# UI.net
KiCad netlist of a schematic drawn in Altium Designer
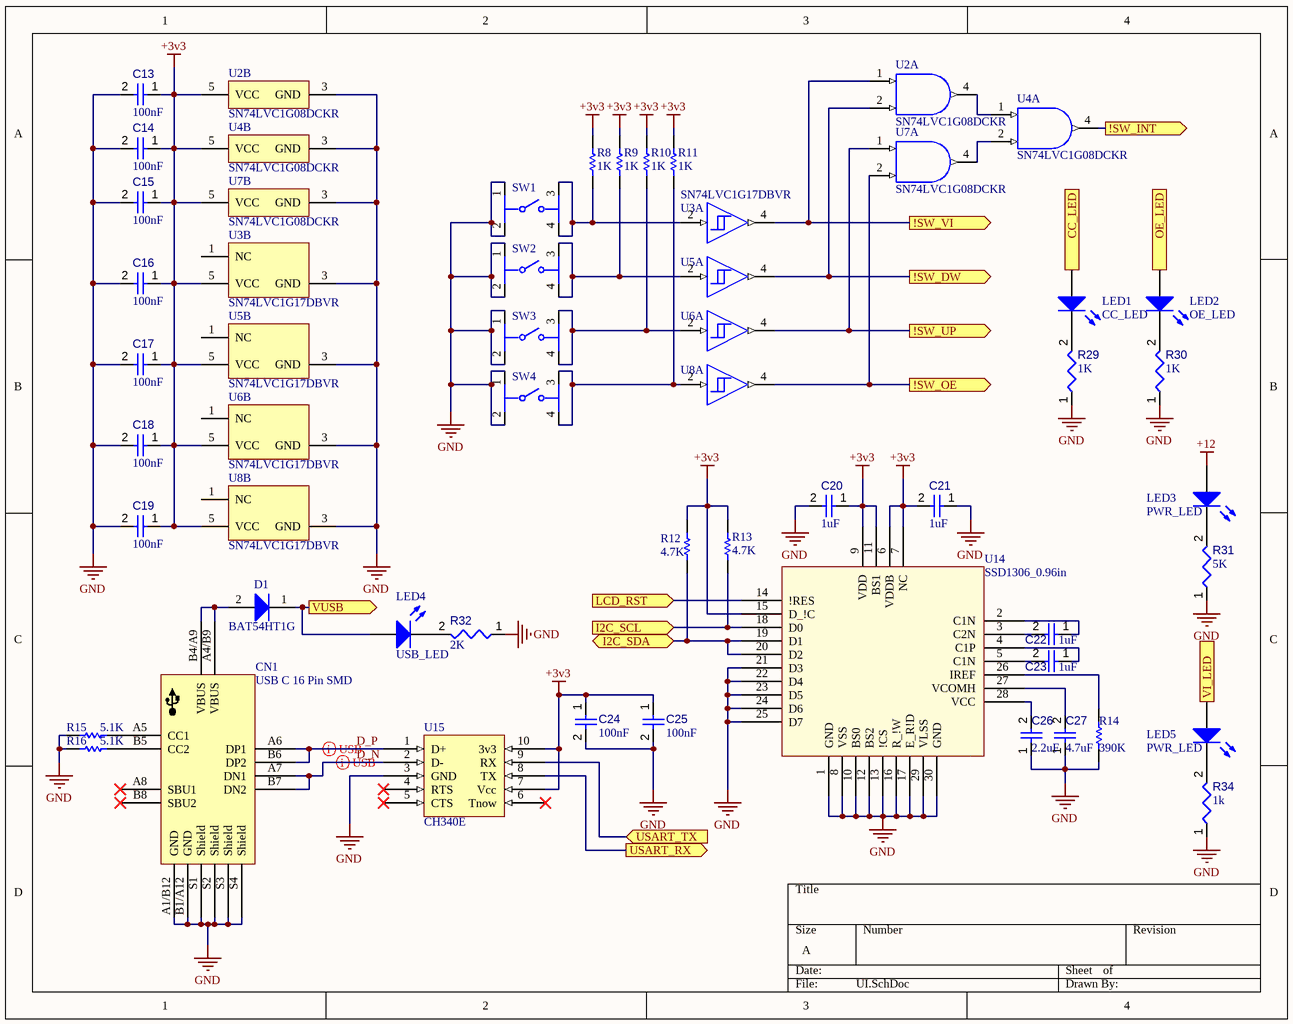
[diagram p0: UI.SchDoc]

(export (version "E")
  (design (tool "Eeschema 10.0.6"))
  (components
    (comp (ref "C13")
      (value "100nF")
      (footprint "CAPC2013X95X50ML10T25")
      (description "Chip Capacitor, 100 nF, +/- 10%, 50 V, 0805 (2012 Metric)")
      (fields (field (name "TOLERANCE") "10%") (field (name "Comment") "Capacitor 100 nF +/-10% 50 V 0805"))
      (libsource (lib "Aditya Sehgal") (part "CAP-NP-2"))
    )
    (comp (ref "C14")
      (value "100nF")
      (footprint "CAPC2013X95X50ML10T25")
      (description "Chip Capacitor, 100 nF, +/- 10%, 50 V, 0805 (2012 Metric)")
      (fields (field (name "TOLERANCE") "10%") (field (name "Comment") "Capacitor 100 nF +/-10% 50 V 0805"))
      (libsource (lib "Aditya Sehgal") (part "CAP-NP-2"))
    )
    (comp (ref "C15")
      (value "100nF")
      (footprint "CAPC2013X95X50ML10T25")
      (description "Chip Capacitor, 100 nF, +/- 10%, 50 V, 0805 (2012 Metric)")
      (fields (field (name "TOLERANCE") "10%") (field (name "Comment") "Capacitor 100 nF +/-10% 50 V 0805"))
      (libsource (lib "Aditya Sehgal") (part "CAP-NP-2"))
    )
    (comp (ref "C16")
      (value "100nF")
      (footprint "CAPC2013X95X50ML10T25")
      (description "Chip Capacitor, 100 nF, +/- 10%, 50 V, 0805 (2012 Metric)")
      (fields (field (name "TOLERANCE") "10%") (field (name "Comment") "Capacitor 100 nF +/-10% 50 V 0805"))
      (libsource (lib "Aditya Sehgal") (part "CAP-NP-2"))
    )
    (comp (ref "C17")
      (value "100nF")
      (footprint "CAPC2013X95X50ML10T25")
      (description "Chip Capacitor, 100 nF, +/- 10%, 50 V, 0805 (2012 Metric)")
      (fields (field (name "TOLERANCE") "10%") (field (name "Comment") "Capacitor 100 nF +/-10% 50 V 0805"))
      (libsource (lib "Aditya Sehgal") (part "CAP-NP-2"))
    )
    (comp (ref "C18")
      (value "100nF")
      (footprint "CAPC2013X95X50ML10T25")
      (description "Chip Capacitor, 100 nF, +/- 10%, 50 V, 0805 (2012 Metric)")
      (fields (field (name "TOLERANCE") "10%") (field (name "Comment") "Capacitor 100 nF +/-10% 50 V 0805"))
      (libsource (lib "Aditya Sehgal") (part "CAP-NP-2"))
    )
    (comp (ref "C19")
      (value "100nF")
      (footprint "CAPC2013X95X50ML10T25")
      (description "Chip Capacitor, 100 nF, +/- 10%, 50 V, 0805 (2012 Metric)")
      (fields (field (name "TOLERANCE") "10%") (field (name "Comment") "Capacitor 100 nF +/-10% 50 V 0805"))
      (libsource (lib "Aditya Sehgal") (part "CAP-NP-2"))
    )
    (comp (ref "C20")
      (value "1uF")
      (footprint "CAPC2013X95X50ML10T25")
      (description "Chip Capacitor, 100 nF, +/- 10%, 50 V, 0805 (2012 Metric)")
      (fields (field (name "TOLERANCE") "10%") (field (name "Comment") "Capacitor 100 nF +/-10% 50 V 0805"))
      (libsource (lib "Aditya Sehgal") (part "CAP-NP-2"))
    )
    (comp (ref "C21")
      (value "1uF")
      (footprint "CAPC2013X95X50ML10T25")
      (description "Chip Capacitor, 100 nF, +/- 10%, 50 V, 0805 (2012 Metric)")
      (fields (field (name "TOLERANCE") "10%") (field (name "Comment") "Capacitor 100 nF +/-10% 50 V 0805"))
      (libsource (lib "Aditya Sehgal") (part "CAP-NP-2"))
    )
    (comp (ref "C22")
      (value "1uF")
      (footprint "CAPC2013X95X50ML10T25")
      (description "Chip Capacitor, 100 nF, +/- 10%, 50 V, 0805 (2012 Metric)")
      (fields (field (name "TOLERANCE") "10%") (field (name "Comment") "Capacitor 100 nF +/-10% 50 V 0805"))
      (libsource (lib "Aditya Sehgal") (part "CAP-NP-2"))
    )
    (comp (ref "C23")
      (value "1uF")
      (footprint "CAPC2013X95X50ML10T25")
      (description "Chip Capacitor, 100 nF, +/- 10%, 50 V, 0805 (2012 Metric)")
      (fields (field (name "TOLERANCE") "10%") (field (name "Comment") "Capacitor 100 nF +/-10% 50 V 0805"))
      (libsource (lib "Aditya Sehgal") (part "CAP-NP-2"))
    )
    (comp (ref "C24")
      (value "100nF")
      (footprint "CAPC2013X95X50ML10T25")
      (description "Chip Capacitor, 100 nF, +/- 10%, 50 V, 0805 (2012 Metric)")
      (fields (field (name "TOLERANCE") "10%") (field (name "Comment") "Capacitor 100 nF +/-10% 50 V 0805"))
      (libsource (lib "Aditya Sehgal") (part "CAP-NP-2"))
    )
    (comp (ref "C25")
      (value "100nF")
      (footprint "CAPC2013X95X50ML10T25")
      (description "Chip Capacitor, 100 nF, +/- 10%, 50 V, 0805 (2012 Metric)")
      (fields (field (name "TOLERANCE") "10%") (field (name "Comment") "Capacitor 100 nF +/-10% 50 V 0805"))
      (libsource (lib "Aditya Sehgal") (part "CAP-NP-2"))
    )
    (comp (ref "C26")
      (value "2.2uF")
      (footprint "CAPC2013X95X50ML10T25")
      (description "Chip Capacitor, 100 nF, +/- 10%, 50 V, 0805 (2012 Metric)")
      (fields (field (name "TOLERANCE") "10%") (field (name "Comment") "Capacitor 100 nF +/-10% 50 V 0805"))
      (libsource (lib "Aditya Sehgal") (part "CAP-NP-2"))
    )
    (comp (ref "C27")
      (value "4.7uF")
      (footprint "CAPC2013X95X50ML10T25")
      (description "Chip Capacitor, 100 nF, +/- 10%, 50 V, 0805 (2012 Metric)")
      (fields (field (name "TOLERANCE") "10%") (field (name "Comment") "Capacitor 100 nF +/-10% 50 V 0805"))
      (libsource (lib "Aditya Sehgal") (part "CAP-NP-2"))
    )
    (comp (ref "CN1")
      (value "USB C 16 Pin SMD")
      (footprint "USB C 16 Pin SMD-Footprint-1")
      (description "C167321 Jing Extension")
      (libsource (lib "Aditya Sehgal") (part "USB C 16 Pin SMD"))
    )
    (comp (ref "D1")
      (value "BAT54HT1G")
      (footprint "ONSC-SOD-323-2-477-02_V")
      (description "Schottky Barrier Diode, 2-Pin SOD-323, Pb-Free, Tape and Reel")
      (fields (field (name "MANUFACTURER") "On Semiconductor"))
      (libsource (lib "Altium Content Vault") (part "ONSC-D-K1A2-2"))
    )
    (comp (ref "LED1")
      (value "CC_LED")
      (footprint "0805_A")
      (description "SMD mono-color Chip LED, WL-SMCW, Super Red")
      (fields (field (name "MANUFACTURER") "Wuerth Elektronik") (field (name "PARTNUMBER") "150080SS75000"))
      (libsource (lib "Altium Content Vault") (part "WE-LED_K1A2-2"))
    )
    (comp (ref "LED2")
      (value "OE_LED")
      (footprint "0805_A")
      (description "SMD mono-color Chip LED, WL-SMCW, Super Red")
      (fields (field (name "MANUFACTURER") "Wuerth Elektronik") (field (name "PARTNUMBER") "150080SS75000"))
      (libsource (lib "Altium Content Vault") (part "WE-LED_K1A2-2"))
    )
    (comp (ref "LED3")
      (value "PWR_LED")
      (footprint "0805_A")
      (description "SMD mono-color Chip LED, WL-SMCW, Super Red")
      (fields (field (name "MANUFACTURER") "Wuerth Elektronik") (field (name "PARTNUMBER") "150080SS75000"))
      (libsource (lib "Altium Content Vault") (part "WE-LED_K1A2-2"))
    )
    (comp (ref "LED4")
      (value "USB_LED")
      (footprint "0805_A")
      (description "SMD mono-color Chip LED, WL-SMCW, Super Red")
      (fields (field (name "MANUFACTURER") "Wuerth Elektronik") (field (name "PARTNUMBER") "150080SS75000"))
      (libsource (lib "Altium Content Vault") (part "WE-LED_K1A2-2"))
    )
    (comp (ref "LED5")
      (value "PWR_LED")
      (footprint "0805_A")
      (description "SMD mono-color Chip LED, WL-SMCW, Super Red")
      (fields (field (name "MANUFACTURER") "Wuerth Elektronik") (field (name "PARTNUMBER") "150080SS75000"))
      (libsource (lib "Altium Content Vault") (part "WE-LED_K1A2-2"))
    )
    (comp (ref "R8")
      (value "1K")
      (footprint "RESC2013X50X35ML15T15")
      (description "Chip Resistor, 0 Ohm, +/- 1%, 125 mW, -55 to 155 degC, 0805 (2012 Metric)")
      (fields (field (name "TOLERANCE") "1%") (field (name "POWER") "125mW"))
      (libsource (lib "Aditya Sehgal") (part "RES-2"))
    )
    (comp (ref "R9")
      (value "1K")
      (footprint "RESC2013X50X35ML15T15")
      (description "Chip Resistor, 0 Ohm, +/- 1%, 125 mW, -55 to 155 degC, 0805 (2012 Metric)")
      (fields (field (name "TOLERANCE") "1%") (field (name "POWER") "125mW"))
      (libsource (lib "Aditya Sehgal") (part "RES-2"))
    )
    (comp (ref "R10")
      (value "1K")
      (footprint "RESC2013X50X35ML15T15")
      (description "Chip Resistor, 0 Ohm, +/- 1%, 125 mW, -55 to 155 degC, 0805 (2012 Metric)")
      (fields (field (name "TOLERANCE") "1%") (field (name "POWER") "125mW"))
      (libsource (lib "Aditya Sehgal") (part "RES-2"))
    )
    (comp (ref "R11")
      (value "1K")
      (footprint "RESC2013X50X35ML15T15")
      (description "Chip Resistor, 0 Ohm, +/- 1%, 125 mW, -55 to 155 degC, 0805 (2012 Metric)")
      (fields (field (name "TOLERANCE") "1%") (field (name "POWER") "125mW"))
      (libsource (lib "Aditya Sehgal") (part "RES-2"))
    )
    (comp (ref "R12")
      (value "4.7K")
      (footprint "RESC2013X50X35ML15T15")
      (description "Chip Resistor, 0 Ohm, +/- 1%, 125 mW, -55 to 155 degC, 0805 (2012 Metric)")
      (fields (field (name "TOLERANCE") "1%") (field (name "POWER") "125mW"))
      (libsource (lib "Aditya Sehgal") (part "RES-2"))
    )
    (comp (ref "R13")
      (value "4.7K")
      (footprint "RESC2013X50X35ML15T15")
      (description "Chip Resistor, 0 Ohm, +/- 1%, 125 mW, -55 to 155 degC, 0805 (2012 Metric)")
      (fields (field (name "TOLERANCE") "1%") (field (name "POWER") "125mW"))
      (libsource (lib "Aditya Sehgal") (part "RES-2"))
    )
    (comp (ref "R14")
      (value "390K")
      (footprint "RESC2013X50X35ML15T15")
      (description "Chip Resistor, 0 Ohm, +/- 1%, 125 mW, -55 to 155 degC, 0805 (2012 Metric)")
      (fields (field (name "TOLERANCE") "1%") (field (name "POWER") "125mW"))
      (libsource (lib "Aditya Sehgal") (part "RES-2"))
    )
    (comp (ref "R15")
      (value "5.1K")
      (footprint "RESC2013X50X35ML15T15")
      (description "Chip Resistor, 0 Ohm, +/- 1%, 125 mW, -55 to 155 degC, 0805 (2012 Metric)")
      (fields (field (name "TOLERANCE") "1%") (field (name "POWER") "125mW"))
      (libsource (lib "Aditya Sehgal") (part "RES-2"))
    )
    (comp (ref "R16")
      (value "5.1K")
      (footprint "RESC2013X50X35ML15T15")
      (description "Chip Resistor, 0 Ohm, +/- 1%, 125 mW, -55 to 155 degC, 0805 (2012 Metric)")
      (fields (field (name "TOLERANCE") "1%") (field (name "POWER") "125mW"))
      (libsource (lib "Aditya Sehgal") (part "RES-2"))
    )
    (comp (ref "R29")
      (value "1K")
      (footprint "RESC0805(2012)_L")
      (description "Chip Resistor, 470 Ohms, +/-5%, 125 mW, -55 to 155 degC, 0805")
      (fields (field (name "POWER") "125mW") (field (name "TOLERANCE") "5%"))
      (libsource (lib "University of California Santa Cruz") (part "RES-2"))
    )
    (comp (ref "R30")
      (value "1K")
      (footprint "RESC0805(2012)_L")
      (description "Chip Resistor, 470 Ohms, +/-5%, 125 mW, -55 to 155 degC, 0805")
      (fields (field (name "POWER") "125mW") (field (name "TOLERANCE") "5%"))
      (libsource (lib "University of California Santa Cruz") (part "RES-2"))
    )
    (comp (ref "R31")
      (value "5K")
      (footprint "RESC0805(2012)_L")
      (description "Chip Resistor, 470 Ohms, +/-5%, 125 mW, -55 to 155 degC, 0805")
      (fields (field (name "POWER") "125mW") (field (name "TOLERANCE") "5%"))
      (libsource (lib "University of California Santa Cruz") (part "RES-2"))
    )
    (comp (ref "R32")
      (value "2K")
      (footprint "RESC0805(2012)_L")
      (description "Chip Resistor, 470 Ohms, +/-5%, 125 mW, -55 to 155 degC, 0805")
      (fields (field (name "POWER") "125mW") (field (name "TOLERANCE") "5%"))
      (libsource (lib "University of California Santa Cruz") (part "RES-2"))
    )
    (comp (ref "R34")
      (value "1k")
      (footprint "RESC0805(2012)_L")
      (description "Chip Resistor, 470 Ohms, +/-5%, 125 mW, -55 to 155 degC, 0805")
      (fields (field (name "POWER") "125mW") (field (name "TOLERANCE") "5%"))
      (libsource (lib "University of California Santa Cruz") (part "RES-2"))
    )
    (comp (ref "SW1")
      (value "PTS526SK15SMTR2LFS")
      (footprint "FP-PTS526SK15SMTR2LFS-MFG")
      (description "Tactile Switch SPST-NO Top Actuated Surface Mount")
      (fields (field (name "MANUFACTURER") "C&K"))
      (libsource (lib "Altium Content Vault") (part "b8895f3f4cefb76e1819d2863dba89b"))
    )
    (comp (ref "SW2")
      (value "PTS526SK15SMTR2LFS")
      (footprint "FP-PTS526SK15SMTR2LFS-MFG")
      (description "Tactile Switch SPST-NO Top Actuated Surface Mount")
      (fields (field (name "MANUFACTURER") "C&K"))
      (libsource (lib "Altium Content Vault") (part "b8895f3f4cefb76e1819d2863dba89b"))
    )
    (comp (ref "SW3")
      (value "PTS526SK15SMTR2LFS")
      (footprint "FP-PTS526SK15SMTR2LFS-MFG")
      (description "Tactile Switch SPST-NO Top Actuated Surface Mount")
      (fields (field (name "MANUFACTURER") "C&K"))
      (libsource (lib "Altium Content Vault") (part "b8895f3f4cefb76e1819d2863dba89b"))
    )
    (comp (ref "SW4")
      (value "PTS526SK15SMTR2LFS")
      (footprint "FP-PTS526SK15SMTR2LFS-MFG")
      (description "Tactile Switch SPST-NO Top Actuated Surface Mount")
      (fields (field (name "MANUFACTURER") "C&K"))
      (libsource (lib "Altium Content Vault") (part "b8895f3f4cefb76e1819d2863dba89b"))
    )
    (comp (ref "U2")
      (value "SN74LVC1G08DCKR")
      (footprint "DCK0005A_M")
      (description "Single 2-Input Positive-AND Gate, DCK0005A, LARGE T&R")
      (fields
        (field (name "GENERIC PART NUMBER") "SN74LVC1G08")
        (field (name "MANUFACTURER") "Texas Instruments")
      )
      (libsource (lib "Altium Content Vault") (part "TI-SN74XXX1X08-5"))
    )
    (comp (ref "U3")
      (value "SN74LVC1G17DBVR")
      (footprint "DBV0005A_L")
      (description "Single Schmitt-Trigger Buffer, DBV0005A, LARGE T&R")
      (fields
        (field (name "MANUFACTURER") "Texas Instruments")
        (field (name "GENERIC PART NUMBER") "SN74LVC1G17")
      )
      (libsource (lib "Altium Content Vault") (part "TI-SN74XXX1XXX-XX-5-SCHMITT"))
    )
    (comp (ref "U4")
      (value "SN74LVC1G08DCKR")
      (footprint "DCK0005A_M")
      (description "Single 2-Input Positive-AND Gate, DCK0005A, LARGE T&R")
      (fields
        (field (name "GENERIC PART NUMBER") "SN74LVC1G08")
        (field (name "MANUFACTURER") "Texas Instruments")
      )
      (libsource (lib "Altium Content Vault") (part "TI-SN74XXX1X08-5"))
    )
    (comp (ref "U5")
      (value "SN74LVC1G17DBVR")
      (footprint "DBV0005A_L")
      (description "Single Schmitt-Trigger Buffer, DBV0005A, LARGE T&R")
      (fields
        (field (name "MANUFACTURER") "Texas Instruments")
        (field (name "GENERIC PART NUMBER") "SN74LVC1G17")
      )
      (libsource (lib "Altium Content Vault") (part "TI-SN74XXX1XXX-XX-5-SCHMITT"))
    )
    (comp (ref "U6")
      (value "SN74LVC1G17DBVR")
      (footprint "DBV0005A_L")
      (description "Single Schmitt-Trigger Buffer, DBV0005A, LARGE T&R")
      (fields
        (field (name "MANUFACTURER") "Texas Instruments")
        (field (name "GENERIC PART NUMBER") "SN74LVC1G17")
      )
      (libsource (lib "Altium Content Vault") (part "TI-SN74XXX1XXX-XX-5-SCHMITT"))
    )
    (comp (ref "U7")
      (value "SN74LVC1G08DCKR")
      (footprint "DCK0005A_M")
      (description "Single 2-Input Positive-AND Gate, DCK0005A, LARGE T&R")
      (fields
        (field (name "GENERIC PART NUMBER") "SN74LVC1G08")
        (field (name "MANUFACTURER") "Texas Instruments")
      )
      (libsource (lib "Altium Content Vault") (part "TI-SN74XXX1X08-5"))
    )
    (comp (ref "U8")
      (value "SN74LVC1G17DBVR")
      (footprint "DBV0005A_L")
      (description "Single Schmitt-Trigger Buffer, DBV0005A, LARGE T&R")
      (fields
        (field (name "MANUFACTURER") "Texas Instruments")
        (field (name "GENERIC PART NUMBER") "SN74LVC1G17")
      )
      (libsource (lib "Altium Content Vault") (part "TI-SN74XXX1XXX-XX-5-SCHMITT"))
    )
    (comp (ref "U14")
      (value "SSD1306_0.96in")
      (footprint "SSD1306_0.96in-Footprint-1")
      (description "C91755")
      (libsource (lib "Aditya Sehgal") (part "SSD1306_0.96in"))
    )
    (comp (ref "U15")
      (value "CH340E")
      (footprint "TSSOP50P490X110-10N")
      (description "USB to UART Converter")
      (libsource (lib "Aditya Sehgal") (part "CH340E"))
    )
  )
  (nets
    (net (code "1") (name "+3v3") (class "Default")
      (node (ref "C13") (pin "1") (pinfunction "1_1") (pintype "passive"))
      (node (ref "C14") (pin "1") (pinfunction "1_1") (pintype "passive"))
      (node (ref "C15") (pin "1") (pinfunction "1_1") (pintype "passive"))
      (node (ref "C16") (pin "1") (pinfunction "1_1") (pintype "passive"))
      (node (ref "C17") (pin "1") (pinfunction "1_1") (pintype "passive"))
      (node (ref "C18") (pin "1") (pinfunction "1_1") (pintype "passive"))
      (node (ref "C19") (pin "1") (pinfunction "1_1") (pintype "passive"))
      (node (ref "C20") (pin "1") (pinfunction "1_1") (pintype "passive"))
      (node (ref "C21") (pin "2") (pinfunction "2_2") (pintype "passive"))
      (node (ref "C24") (pin "1") (pinfunction "1_1") (pintype "passive"))
      (node (ref "C25") (pin "1") (pinfunction "1_1") (pintype "passive"))
      (node (ref "R10") (pin "2") (pinfunction "2_2") (pintype "passive"))
      (node (ref "R11") (pin "2") (pinfunction "2_2") (pintype "passive"))
      (node (ref "R12") (pin "2") (pinfunction "2_2") (pintype "passive"))
      (node (ref "R13") (pin "2") (pinfunction "2_2") (pintype "passive"))
      (node (ref "R8") (pin "2") (pinfunction "2_2") (pintype "passive"))
      (node (ref "R9") (pin "2") (pinfunction "2_2") (pintype "passive"))
      (node (ref "U14") (pin "11") (pinfunction "BS1_11") (pintype "passive"))
      (node (ref "U14") (pin "15") (pinfunction "D_!C_15") (pintype "passive"))
      (node (ref "U14") (pin "6") (pinfunction "VDDB_6") (pintype "passive"))
      (node (ref "U14") (pin "7") (pinfunction "NC_7") (pintype "passive"))
      (node (ref "U14") (pin "9") (pinfunction "VDD_9") (pintype "passive"))
      (node (ref "U15") (pin "10") (pinfunction "3v3_10") (pintype "input"))
      (node (ref "U15") (pin "7") (pinfunction "Vcc_7") (pintype "input"))
      (node (ref "U2") (pin "5") (pinfunction "VCC_5") (pintype "power_in"))
      (node (ref "U3") (pin "5") (pinfunction "VCC_5") (pintype "power_in"))
      (node (ref "U4") (pin "5") (pinfunction "VCC_5") (pintype "power_in"))
      (node (ref "U5") (pin "5") (pinfunction "VCC_5") (pintype "power_in"))
      (node (ref "U6") (pin "5") (pinfunction "VCC_5") (pintype "power_in"))
      (node (ref "U7") (pin "5") (pinfunction "VCC_5") (pintype "power_in"))
      (node (ref "U8") (pin "5") (pinfunction "VCC_5") (pintype "power_in"))
    )
    (net (code "2") (name "+12") (class "Default")
      (node (ref "LED3") (pin "2") (pinfunction "A_2") (pintype "passive"))
    )
    (net (code "3") (name "/!SW_DW") (class "Default")
      (node (ref "U2") (pin "2") (pinfunction "B_2") (pintype "input"))
      (node (ref "U5") (pin "4") (pinfunction "Y_4") (pintype "output"))
    )
    (net (code "4") (name "/!SW_INT") (class "Default")
      (node (ref "U4") (pin "4") (pinfunction "Y_4") (pintype "output"))
    )
    (net (code "5") (name "/!SW_OE") (class "Default")
      (node (ref "U7") (pin "2") (pinfunction "B_2") (pintype "input"))
      (node (ref "U8") (pin "4") (pinfunction "Y_4") (pintype "output"))
    )
    (net (code "6") (name "/!SW_UP") (class "Default")
      (node (ref "U6") (pin "4") (pinfunction "Y_4") (pintype "output"))
      (node (ref "U7") (pin "1") (pinfunction "A_1") (pintype "input"))
    )
    (net (code "7") (name "/!SW_VI") (class "Default")
      (node (ref "U2") (pin "1") (pinfunction "A_1") (pintype "input"))
      (node (ref "U3") (pin "4") (pinfunction "Y_4") (pintype "output"))
    )
    (net (code "8") (name "/CC_LED") (class "Default")
      (node (ref "LED1") (pin "2") (pinfunction "A_2") (pintype "passive"))
    )
    (net (code "9") (name "/D_N") (class "Default")
      (node (ref "CN1") (pin "A7") (pinfunction "DN1_A7") (pintype "passive"))
      (node (ref "CN1") (pin "B7") (pinfunction "DN2_B7") (pintype "passive"))
      (node (ref "U15") (pin "2") (pinfunction "D-_2") (pintype "input"))
    )
    (net (code "10") (name "/D_P") (class "Default")
      (node (ref "CN1") (pin "A6") (pinfunction "DP1_A6") (pintype "passive"))
      (node (ref "CN1") (pin "B6") (pinfunction "DP2_B6") (pintype "passive"))
      (node (ref "U15") (pin "1") (pinfunction "D+_1") (pintype "input"))
    )
    (net (code "11") (name "/I2C_SCL") (class "Default")
      (node (ref "R13") (pin "1") (pinfunction "1_1") (pintype "passive"))
      (node (ref "U14") (pin "18") (pinfunction "D0_18") (pintype "passive"))
    )
    (net (code "12") (name "/I2C_SDA") (class "Default")
      (node (ref "R12") (pin "1") (pinfunction "1_1") (pintype "passive"))
      (node (ref "U14") (pin "19") (pinfunction "D1_19") (pintype "passive"))
      (node (ref "U14") (pin "20") (pinfunction "D2_20") (pintype "passive"))
    )
    (net (code "13") (name "/LCD_RST") (class "Default")
      (node (ref "U14") (pin "14") (pinfunction "!RES_14") (pintype "passive"))
    )
    (net (code "14") (name "/OE_LED") (class "Default")
      (node (ref "LED2") (pin "2") (pinfunction "A_2") (pintype "passive"))
    )
    (net (code "15") (name "/USART_RX") (class "Default")
      (node (ref "U15") (pin "8") (pinfunction "TX_8") (pintype "input"))
    )
    (net (code "16") (name "/USART_TX") (class "Default")
      (node (ref "U15") (pin "9") (pinfunction "RX_9") (pintype "input"))
    )
    (net (code "17") (name "/VI_LED") (class "Default")
      (node (ref "LED5") (pin "2") (pinfunction "A_2") (pintype "passive"))
    )
    (net (code "18") (name "/VUSB") (class "Default")
      (node (ref "D1") (pin "1") (pinfunction "K_1") (pintype "passive"))
      (node (ref "LED4") (pin "2") (pinfunction "A_2") (pintype "passive"))
    )
    (net (code "19") (name "GND") (class "Default")
      (node (ref "C13") (pin "2") (pinfunction "2_2") (pintype "passive"))
      (node (ref "C14") (pin "2") (pinfunction "2_2") (pintype "passive"))
      (node (ref "C15") (pin "2") (pinfunction "2_2") (pintype "passive"))
      (node (ref "C16") (pin "2") (pinfunction "2_2") (pintype "passive"))
      (node (ref "C17") (pin "2") (pinfunction "2_2") (pintype "passive"))
      (node (ref "C18") (pin "2") (pinfunction "2_2") (pintype "passive"))
      (node (ref "C19") (pin "2") (pinfunction "2_2") (pintype "passive"))
      (node (ref "C20") (pin "2") (pinfunction "2_2") (pintype "passive"))
      (node (ref "C21") (pin "1") (pinfunction "1_1") (pintype "passive"))
      (node (ref "C24") (pin "2") (pinfunction "2_2") (pintype "passive"))
      (node (ref "C25") (pin "2") (pinfunction "2_2") (pintype "passive"))
      (node (ref "C26") (pin "1") (pinfunction "1_1") (pintype "passive"))
      (node (ref "C27") (pin "1") (pinfunction "1_1") (pintype "passive"))
      (node (ref "CN1") (pin "A1/B12") (pinfunction "GND_A1/B12") (pintype "power_in"))
      (node (ref "CN1") (pin "B1/A12") (pinfunction "GND_B1/A12") (pintype "power_in"))
      (node (ref "CN1") (pin "S1") (pinfunction "Shield_S1") (pintype "power_in"))
      (node (ref "CN1") (pin "S2") (pinfunction "Shield_S2") (pintype "power_in"))
      (node (ref "CN1") (pin "S3") (pinfunction "Shield_S3") (pintype "power_in"))
      (node (ref "CN1") (pin "S4") (pinfunction "Shield_S4") (pintype "power_in"))
      (node (ref "R14") (pin "2") (pinfunction "2_2") (pintype "passive"))
      (node (ref "R15") (pin "2") (pinfunction "2_2") (pintype "passive"))
      (node (ref "R16") (pin "2") (pinfunction "2_2") (pintype "passive"))
      (node (ref "R29") (pin "1") (pinfunction "1_1") (pintype "passive"))
      (node (ref "R30") (pin "1") (pinfunction "1_1") (pintype "passive"))
      (node (ref "R31") (pin "1") (pinfunction "1_1") (pintype "passive"))
      (node (ref "R32") (pin "1") (pinfunction "1_1") (pintype "passive"))
      (node (ref "R34") (pin "1") (pinfunction "1_1") (pintype "passive"))
      (node (ref "SW1") (pin "1") (pinfunction "1_1") (pintype "passive"))
      (node (ref "SW1") (pin "2") (pinfunction "2_2") (pintype "passive"))
      (node (ref "SW2") (pin "1") (pinfunction "1_1") (pintype "passive"))
      (node (ref "SW2") (pin "2") (pinfunction "2_2") (pintype "passive"))
      (node (ref "SW3") (pin "1") (pinfunction "1_1") (pintype "passive"))
      (node (ref "SW3") (pin "2") (pinfunction "2_2") (pintype "passive"))
      (node (ref "SW4") (pin "1") (pinfunction "1_1") (pintype "passive"))
      (node (ref "SW4") (pin "2") (pinfunction "2_2") (pintype "passive"))
      (node (ref "U14") (pin "1") (pinfunction "GND_1") (pintype "passive"))
      (node (ref "U14") (pin "10") (pinfunction "BS0_10") (pintype "passive"))
      (node (ref "U14") (pin "12") (pinfunction "BS2_12") (pintype "passive"))
      (node (ref "U14") (pin "13") (pinfunction "!CS_13") (pintype "passive"))
      (node (ref "U14") (pin "16") (pinfunction "R_!W_16") (pintype "passive"))
      (node (ref "U14") (pin "17") (pinfunction "E_R!D_17") (pintype "passive"))
      (node (ref "U14") (pin "21") (pinfunction "D3_21") (pintype "passive"))
      (node (ref "U14") (pin "22") (pinfunction "D4_22") (pintype "passive"))
      (node (ref "U14") (pin "23") (pinfunction "D5_23") (pintype "passive"))
      (node (ref "U14") (pin "24") (pinfunction "D6_24") (pintype "passive"))
      (node (ref "U14") (pin "25") (pinfunction "D7_25") (pintype "passive"))
      (node (ref "U14") (pin "29") (pinfunction "VLSS_29") (pintype "passive"))
      (node (ref "U14") (pin "30") (pinfunction "GND_30") (pintype "passive"))
      (node (ref "U14") (pin "8") (pinfunction "VSS_8") (pintype "passive"))
      (node (ref "U15") (pin "3") (pinfunction "GND_3") (pintype "input"))
      (node (ref "U2") (pin "3") (pinfunction "GND_3") (pintype "power_in"))
      (node (ref "U3") (pin "3") (pinfunction "GND_3") (pintype "power_in"))
      (node (ref "U4") (pin "3") (pinfunction "GND_3") (pintype "power_in"))
      (node (ref "U5") (pin "3") (pinfunction "GND_3") (pintype "power_in"))
      (node (ref "U6") (pin "3") (pinfunction "GND_3") (pintype "power_in"))
      (node (ref "U7") (pin "3") (pinfunction "GND_3") (pintype "power_in"))
      (node (ref "U8") (pin "3") (pinfunction "GND_3") (pintype "power_in"))
    )
    (net (code "20") (name "Net-(C22-Pad1)") (class "Default")
      (node (ref "C22") (pin "1") (pinfunction "1_1") (pintype "passive"))
      (node (ref "U14") (pin "2") (pinfunction "C1N_2") (pintype "passive"))
    )
    (net (code "21") (name "Net-(C23-Pad2)") (class "Default")
      (node (ref "C23") (pin "2") (pinfunction "2_2") (pintype "passive"))
      (node (ref "U14") (pin "5") (pinfunction "C1N_5") (pintype "passive"))
    )
    (net (code "22") (name "Net-(CN1-CC1)") (class "Default")
      (node (ref "CN1") (pin "A5") (pinfunction "CC1_A5") (pintype "passive"))
      (node (ref "R15") (pin "1") (pinfunction "1_1") (pintype "passive"))
    )
    (net (code "23") (name "Net-(CN1-CC2)") (class "Default")
      (node (ref "CN1") (pin "B5") (pinfunction "CC2_B5") (pintype "passive"))
      (node (ref "R16") (pin "1") (pinfunction "1_1") (pintype "passive"))
    )
    (net (code "24") (name "Net-(D1-A)") (class "Default")
      (node (ref "CN1") (pin "A4/B9") (pinfunction "VBUS_A4/B9") (pintype "power_in"))
      (node (ref "CN1") (pin "B4/A9") (pinfunction "VBUS_B4/A9") (pintype "power_in"))
      (node (ref "D1") (pin "2") (pinfunction "A_2") (pintype "passive"))
    )
    (net (code "25") (name "Net-(LED1-K)") (class "Default")
      (node (ref "LED1") (pin "1") (pinfunction "K_1") (pintype "passive"))
      (node (ref "R29") (pin "2") (pinfunction "2_2") (pintype "passive"))
    )
    (net (code "26") (name "Net-(LED2-K)") (class "Default")
      (node (ref "LED2") (pin "1") (pinfunction "K_1") (pintype "passive"))
      (node (ref "R30") (pin "2") (pinfunction "2_2") (pintype "passive"))
    )
    (net (code "27") (name "Net-(LED3-K)") (class "Default")
      (node (ref "LED3") (pin "1") (pinfunction "K_1") (pintype "passive"))
      (node (ref "R31") (pin "2") (pinfunction "2_2") (pintype "passive"))
    )
    (net (code "28") (name "Net-(LED4-K)") (class "Default")
      (node (ref "LED4") (pin "1") (pinfunction "K_1") (pintype "passive"))
      (node (ref "R32") (pin "2") (pinfunction "2_2") (pintype "passive"))
    )
    (net (code "29") (name "Net-(LED5-K)") (class "Default")
      (node (ref "LED5") (pin "1") (pinfunction "K_1") (pintype "passive"))
      (node (ref "R34") (pin "2") (pinfunction "2_2") (pintype "passive"))
    )
    (net (code "30") (name "Net-(U2A-Y)") (class "Default")
      (node (ref "U2") (pin "4") (pinfunction "Y_4") (pintype "output"))
      (node (ref "U4") (pin "1") (pinfunction "A_1") (pintype "input"))
    )
    (net (code "31") (name "Net-(U3A-A)") (class "Default")
      (node (ref "R8") (pin "1") (pinfunction "1_1") (pintype "passive"))
      (node (ref "SW1") (pin "3") (pinfunction "3_3") (pintype "passive"))
      (node (ref "SW1") (pin "4") (pinfunction "4_4") (pintype "passive"))
      (node (ref "U3") (pin "2") (pinfunction "A_2") (pintype "input"))
    )
    (net (code "32") (name "Net-(U4A-B)") (class "Default")
      (node (ref "U4") (pin "2") (pinfunction "B_2") (pintype "input"))
      (node (ref "U7") (pin "4") (pinfunction "Y_4") (pintype "output"))
    )
    (net (code "33") (name "Net-(U5A-A)") (class "Default")
      (node (ref "R9") (pin "1") (pinfunction "1_1") (pintype "passive"))
      (node (ref "SW2") (pin "3") (pinfunction "3_3") (pintype "passive"))
      (node (ref "SW2") (pin "4") (pinfunction "4_4") (pintype "passive"))
      (node (ref "U5") (pin "2") (pinfunction "A_2") (pintype "input"))
    )
    (net (code "34") (name "Net-(U6A-A)") (class "Default")
      (node (ref "R10") (pin "1") (pinfunction "1_1") (pintype "passive"))
      (node (ref "SW3") (pin "3") (pinfunction "3_3") (pintype "passive"))
      (node (ref "SW3") (pin "4") (pinfunction "4_4") (pintype "passive"))
      (node (ref "U6") (pin "2") (pinfunction "A_2") (pintype "input"))
    )
    (net (code "35") (name "Net-(U8A-A)") (class "Default")
      (node (ref "R11") (pin "1") (pinfunction "1_1") (pintype "passive"))
      (node (ref "SW4") (pin "3") (pinfunction "3_3") (pintype "passive"))
      (node (ref "SW4") (pin "4") (pinfunction "4_4") (pintype "passive"))
      (node (ref "U8") (pin "2") (pinfunction "A_2") (pintype "input"))
    )
    (net (code "36") (name "Net-(U14-C1P)") (class "Default")
      (node (ref "C23") (pin "1") (pinfunction "1_1") (pintype "passive"))
      (node (ref "U14") (pin "4") (pinfunction "C1P_4") (pintype "passive"))
    )
    (net (code "37") (name "Net-(U14-C2N)") (class "Default")
      (node (ref "C22") (pin "2") (pinfunction "2_2") (pintype "passive"))
      (node (ref "U14") (pin "3") (pinfunction "C2N_3") (pintype "passive"))
    )
    (net (code "38") (name "Net-(U14-IREF)") (class "Default")
      (node (ref "R14") (pin "1") (pinfunction "1_1") (pintype "passive"))
      (node (ref "U14") (pin "26") (pinfunction "IREF_26") (pintype "passive"))
    )
    (net (code "39") (name "Net-(U14-VCC)") (class "Default")
      (node (ref "C26") (pin "2") (pinfunction "2_2") (pintype "passive"))
      (node (ref "U14") (pin "28") (pinfunction "VCC_28") (pintype "passive"))
    )
    (net (code "40") (name "Net-(U14-VCOMH)") (class "Default")
      (node (ref "C27") (pin "2") (pinfunction "2_2") (pintype "passive"))
      (node (ref "U14") (pin "27") (pinfunction "VCOMH_27") (pintype "passive"))
    )
    (net (code "41") (name "unconnected-(CN1-S5-PadH2)") (class "Default")
      (node (ref "CN1") (pin "H2") (pinfunction "S5_H2") (pintype "passive"))
    )
    (net (code "42") (name "unconnected-(CN1-S6-PadH1)") (class "Default")
      (node (ref "CN1") (pin "H1") (pinfunction "S6_H1") (pintype "passive"))
    )
    (net (code "43") (name "unconnected-(CN1-SBU1-PadA8)") (class "Default")
      (node (ref "CN1") (pin "A8") (pinfunction "SBU1_A8") (pintype "passive+no_connect"))
    )
    (net (code "44") (name "unconnected-(CN1-SBU2-PadB8)") (class "Default")
      (node (ref "CN1") (pin "B8") (pinfunction "SBU2_B8") (pintype "passive+no_connect"))
    )
    (net (code "45") (name "unconnected-(U3B-NC-Pad1)") (class "Default")
      (node (ref "U3") (pin "1") (pinfunction "NC_1") (pintype "passive"))
    )
    (net (code "46") (name "unconnected-(U5B-NC-Pad1)") (class "Default")
      (node (ref "U5") (pin "1") (pinfunction "NC_1") (pintype "passive"))
    )
    (net (code "47") (name "unconnected-(U6B-NC-Pad1)") (class "Default")
      (node (ref "U6") (pin "1") (pinfunction "NC_1") (pintype "passive"))
    )
    (net (code "48") (name "unconnected-(U8B-NC-Pad1)") (class "Default")
      (node (ref "U8") (pin "1") (pinfunction "NC_1") (pintype "passive"))
    )
    (net (code "49") (name "unconnected-(U14-mech-Pad31)") (class "Default")
      (node (ref "U14") (pin "31") (pinfunction "mech_31") (pintype "passive"))
    )
    (net (code "50") (name "unconnected-(U15-CTS-Pad5)") (class "Default")
      (node (ref "U15") (pin "5") (pinfunction "CTS_5") (pintype "input+no_connect"))
    )
    (net (code "51") (name "unconnected-(U15-RTS-Pad4)") (class "Default")
      (node (ref "U15") (pin "4") (pinfunction "RTS_4") (pintype "input+no_connect"))
    )
    (net (code "52") (name "unconnected-(U15-Tnow-Pad6)") (class "Default")
      (node (ref "U15") (pin "6") (pinfunction "Tnow_6") (pintype "input+no_connect"))
    )
  )
)
